# Motor_Driver_HIP4082_Board_V1_1.net
KiCad netlist of a schematic drawn in Altium Designer
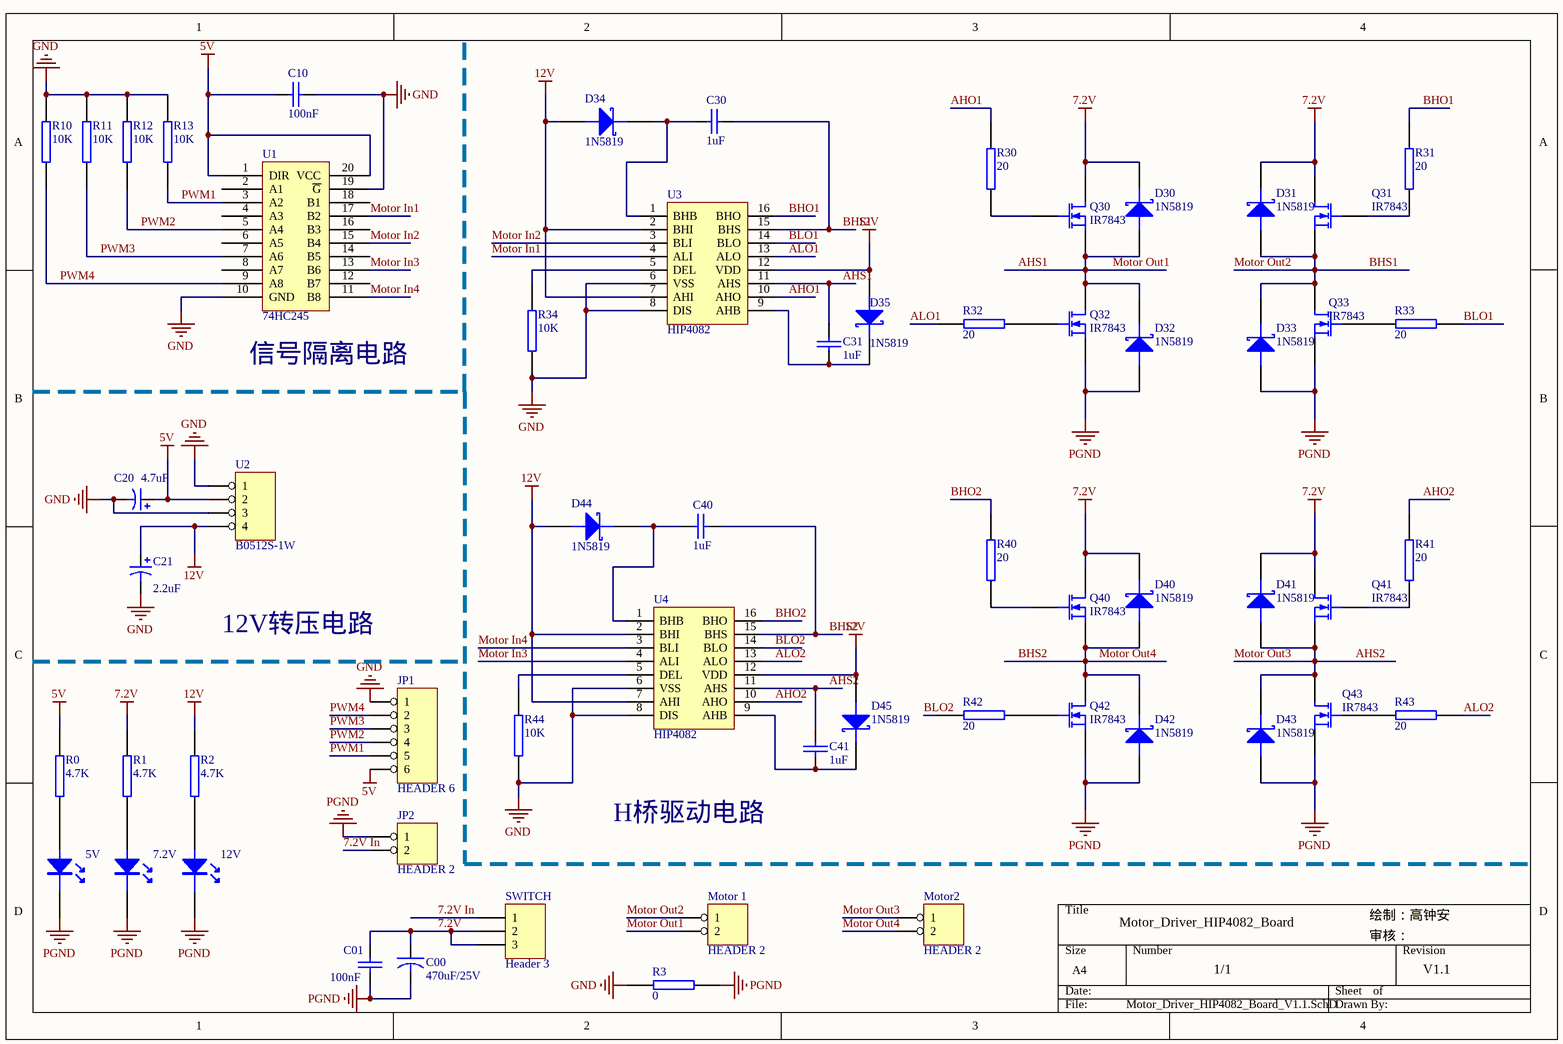
[diagram p0: Motor_Driver_HIP4082_Board_V1.1.SchDoc]

(export (version "E")
  (design (tool "Eeschema 10.0.6"))
  (components
    (comp (ref "5V") (value "~") (footprint "0805_LED_S1") (libsource (lib "Protel99Lib_SCH") (part "LED")))
    (comp (ref "7.2V") (value "~") (footprint "0805_LED_S1") (libsource (lib "Protel99Lib_SCH") (part "LED")))
    (comp (ref "12V") (value "~") (footprint "0805_LED_S1") (libsource (lib "Protel99Lib_SCH") (part "LED")))
    (comp (ref "C00")
      (value "470uF/25V")
      (footprint "RB.2/.4")
      (description "Capacitor")
      (libsource (lib "Protel99Lib_SCH") (part "CAPACITOR"))
    )
    (comp (ref "C01")
      (value "100nF")
      (footprint "0805C")
      (description "Capacitor")
      (libsource (lib "Protel99Lib_SCH") (part "CAP"))
    )
    (comp (ref "C10")
      (value "100nF")
      (footprint "0805C")
      (description "Capacitor")
      (libsource (lib "Protel99Lib_SCH") (part "CAP"))
    )
    (comp (ref "C20")
      (value "4.7uF")
      (footprint "3528")
      (description "Polarized Capacitor (Surface Mount)")
      (fields (field (name "PUBLISHER") "Altium Limited"))
      (libsource (lib "Miscellaneous Devices") (part "Cap Pol3"))
    )
    (comp (ref "C21")
      (value "2.2uF")
      (footprint "3528")
      (description "Polarized Capacitor (Surface Mount)")
      (fields (field (name "PUBLISHER") "Altium Limited"))
      (libsource (lib "Miscellaneous Devices") (part "Cap Pol3"))
    )
    (comp (ref "C30")
      (value "1uF")
      (footprint "0805C")
      (description "Capacitor")
      (libsource (lib "Protel99Lib_SCH") (part "CAP"))
    )
    (comp (ref "C31")
      (value "1uF")
      (footprint "0805C")
      (description "Capacitor")
      (libsource (lib "Protel99Lib_SCH") (part "CAP"))
    )
    (comp (ref "C40")
      (value "1uF")
      (footprint "0805C")
      (description "Capacitor")
      (libsource (lib "Protel99Lib_SCH") (part "CAP"))
    )
    (comp (ref "C41")
      (value "1uF")
      (footprint "0805C")
      (description "Capacitor")
      (libsource (lib "Protel99Lib_SCH") (part "CAP"))
    )
    (comp (ref "D30")
      (value "1N5819")
      (footprint "SOD-323")
      (description "Schottky Diode")
      (libsource (lib "Protel99Lib_SCH") (part "DIODE SCHOTTKY"))
    )
    (comp (ref "D31")
      (value "1N5819")
      (footprint "SOD-323")
      (description "Schottky Diode")
      (libsource (lib "Protel99Lib_SCH") (part "DIODE SCHOTTKY"))
    )
    (comp (ref "D32")
      (value "1N5819")
      (footprint "SOD-323")
      (description "Schottky Diode")
      (libsource (lib "Protel99Lib_SCH") (part "DIODE SCHOTTKY"))
    )
    (comp (ref "D33")
      (value "1N5819")
      (footprint "SOD-323")
      (description "Schottky Diode")
      (libsource (lib "Protel99Lib_SCH") (part "DIODE SCHOTTKY"))
    )
    (comp (ref "D34")
      (value "1N5819")
      (footprint "SOD-323")
      (description "Schottky Diode")
      (libsource (lib "Protel99Lib_SCH") (part "DIODE SCHOTTKY"))
    )
    (comp (ref "D35")
      (value "1N5819")
      (footprint "SOD-323")
      (description "Schottky Diode")
      (libsource (lib "Protel99Lib_SCH") (part "DIODE SCHOTTKY"))
    )
    (comp (ref "D40")
      (value "1N5819")
      (footprint "SOD-323")
      (description "Schottky Diode")
      (libsource (lib "Protel99Lib_SCH") (part "DIODE SCHOTTKY"))
    )
    (comp (ref "D41")
      (value "1N5819")
      (footprint "SOD-323")
      (description "Schottky Diode")
      (libsource (lib "Protel99Lib_SCH") (part "DIODE SCHOTTKY"))
    )
    (comp (ref "D42")
      (value "1N5819")
      (footprint "SOD-323")
      (description "Schottky Diode")
      (libsource (lib "Protel99Lib_SCH") (part "DIODE SCHOTTKY"))
    )
    (comp (ref "D43")
      (value "1N5819")
      (footprint "SOD-323")
      (description "Schottky Diode")
      (libsource (lib "Protel99Lib_SCH") (part "DIODE SCHOTTKY"))
    )
    (comp (ref "D44")
      (value "1N5819")
      (footprint "SOD-323")
      (description "Schottky Diode")
      (libsource (lib "Protel99Lib_SCH") (part "DIODE SCHOTTKY"))
    )
    (comp (ref "D45")
      (value "1N5819")
      (footprint "SOD-323")
      (description "Schottky Diode")
      (libsource (lib "Protel99Lib_SCH") (part "DIODE SCHOTTKY"))
    )
    (comp (ref "JP1")
      (value "HEADER 6")
      (footprint "SIP6N")
      (libsource (lib "Protel99Lib_SCH") (part "HEADER 6"))
    )
    (comp (ref "JP2")
      (value "HEADER 2")
      (footprint "KF301-2P")
      (libsource (lib "Protel99Lib_SCH") (part "HEADER 2"))
    )
    (comp (ref "Motor 1")
      (value "HEADER 2")
      (footprint "KF301-2P")
      (libsource (lib "Protel99Lib_SCH") (part "HEADER 2"))
    )
    (comp (ref "Motor2")
      (value "HEADER 2")
      (footprint "KF301-2P")
      (libsource (lib "Protel99Lib_SCH") (part "HEADER 2"))
    )
    (comp (ref "Q30")
      (value "IR7843")
      (footprint "LR7843")
      (description "N-Channel MOSFET")
      (fields (field (name "PUBLISHER") "Altium Limited"))
      (libsource (lib "Miscellaneous Devices") (part "MOSFET-N"))
    )
    (comp (ref "Q31")
      (value "IR7843")
      (footprint "LR7843")
      (description "N-Channel MOSFET")
      (fields (field (name "PUBLISHER") "Altium Limited"))
      (libsource (lib "Miscellaneous Devices") (part "MOSFET-N"))
    )
    (comp (ref "Q32")
      (value "IR7843")
      (footprint "LR7843")
      (description "N-Channel MOSFET")
      (fields (field (name "PUBLISHER") "Altium Limited"))
      (libsource (lib "Miscellaneous Devices") (part "MOSFET-N"))
    )
    (comp (ref "Q33")
      (value "IR7843")
      (footprint "LR7843")
      (description "N-Channel MOSFET")
      (fields (field (name "PUBLISHER") "Altium Limited"))
      (libsource (lib "Miscellaneous Devices") (part "MOSFET-N"))
    )
    (comp (ref "Q40")
      (value "IR7843")
      (footprint "LR7843")
      (description "N-Channel MOSFET")
      (fields (field (name "PUBLISHER") "Altium Limited"))
      (libsource (lib "Miscellaneous Devices") (part "MOSFET-N"))
    )
    (comp (ref "Q41")
      (value "IR7843")
      (footprint "LR7843")
      (description "N-Channel MOSFET")
      (fields (field (name "PUBLISHER") "Altium Limited"))
      (libsource (lib "Miscellaneous Devices") (part "MOSFET-N"))
    )
    (comp (ref "Q42")
      (value "IR7843")
      (footprint "LR7843")
      (description "N-Channel MOSFET")
      (fields (field (name "PUBLISHER") "Altium Limited"))
      (libsource (lib "Miscellaneous Devices") (part "MOSFET-N"))
    )
    (comp (ref "Q43")
      (value "IR7843")
      (footprint "LR7843")
      (description "N-Channel MOSFET")
      (fields (field (name "PUBLISHER") "Altium Limited"))
      (libsource (lib "Miscellaneous Devices") (part "MOSFET-N"))
    )
    (comp (ref "R0") (value "4.7K") (footprint "0603_R") (libsource (lib "Protel99Lib_SCH") (part "RES2")))
    (comp (ref "R1") (value "4.7K") (footprint "0603_R") (libsource (lib "Protel99Lib_SCH") (part "RES2")))
    (comp (ref "R2") (value "4.7K") (footprint "0603_R") (libsource (lib "Protel99Lib_SCH") (part "RES2")))
    (comp (ref "R3") (value "0") (footprint "0805R") (libsource (lib "Protel99Lib_SCH") (part "RES2")))
    (comp (ref "R10") (value "10K") (footprint "0603_R") (libsource (lib "") (part "RES2_1")))
    (comp (ref "R11") (value "10K") (footprint "0603_R") (libsource (lib "") (part "RES2_1")))
    (comp (ref "R12") (value "10K") (footprint "0603_R") (libsource (lib "") (part "RES2_1")))
    (comp (ref "R13") (value "10K") (footprint "0603_R") (libsource (lib "") (part "RES2_1")))
    (comp (ref "R30") (value "20") (footprint "0805") (libsource (lib "Protel99Lib_SCH") (part "RES2")))
    (comp (ref "R31") (value "20") (footprint "0805") (libsource (lib "Protel99Lib_SCH") (part "RES2")))
    (comp (ref "R32") (value "20") (footprint "0805") (libsource (lib "Protel99Lib_SCH") (part "RES2")))
    (comp (ref "R33") (value "20") (footprint "0805") (libsource (lib "Protel99Lib_SCH") (part "RES2")))
    (comp (ref "R34") (value "10K") (footprint "0603_R") (libsource (lib "Protel99Lib_SCH") (part "RES2")))
    (comp (ref "R40") (value "20") (footprint "0805") (libsource (lib "Protel99Lib_SCH") (part "RES2")))
    (comp (ref "R41") (value "20") (footprint "0805") (libsource (lib "Protel99Lib_SCH") (part "RES2")))
    (comp (ref "R42") (value "20") (footprint "0805") (libsource (lib "Protel99Lib_SCH") (part "RES2")))
    (comp (ref "R43") (value "20") (footprint "0805") (libsource (lib "Protel99Lib_SCH") (part "RES2")))
    (comp (ref "R44") (value "10K") (footprint "0603_R") (libsource (lib "Protel99Lib_SCH") (part "RES2")))
    (comp (ref "SWITCH")
      (value "Header 3")
      (footprint "KEY-3P")
      (description "Header, 3-Pin")
      (fields (field (name "PUBLISHER") "Altium Limited"))
      (libsource (lib "Miscellaneous Connectors") (part "Header 3"))
    )
    (comp (ref "U1") (value "74HC245") (footprint "SOP20") (libsource (lib "BaseLib_SCH") (part "74HC245")))
    (comp (ref "U2")
      (value "B0512S-1W")
      (footprint "SIP4_B_S-1W")
      (description "4 Pin Header")
      (libsource (lib "Protel99Lib_SCH") (part "4 HEADER"))
    )
    (comp (ref "U3")
      (value "HIP4082")
      (footprint "SOP-16_208mil")
      (libsource (lib "Motor_Driver_HIP4082_Board_V1.0") (part "HIP4082"))
    )
    (comp (ref "U4")
      (value "HIP4082")
      (footprint "SOP-16_208mil")
      (libsource (lib "Motor_Driver_HIP4082_Board_V1.0") (part "HIP4082"))
    )
  )
  (nets
    (net (code "1") (name "/7.2V In") (class "Default")
      (node (ref "JP2") (pin "2") (pinfunction "2_2") (pintype "passive"))
      (node (ref "SWITCH") (pin "1") (pinfunction "1_1") (pintype "passive"))
    )
    (net (code "2") (name "/AHO1") (class "Default")
      (node (ref "R30") (pin "2") (pinfunction "2_2") (pintype "passive"))
      (node (ref "U3") (pin "10") (pinfunction "AHO_10") (pintype "passive"))
    )
    (net (code "3") (name "/AHO2") (class "Default")
      (node (ref "R41") (pin "2") (pinfunction "2_2") (pintype "passive"))
      (node (ref "U4") (pin "10") (pinfunction "AHO_10") (pintype "passive"))
    )
    (net (code "4") (name "/AHS1") (class "Default")
      (node (ref "C31") (pin "2") (pinfunction "2_2") (pintype "passive"))
      (node (ref "D30") (pin "1") (pinfunction "A_1") (pintype "passive"))
      (node (ref "D32") (pin "2") (pinfunction "K_2") (pintype "passive"))
      (node (ref "Motor 1") (pin "2") (pinfunction "2_2") (pintype "passive"))
      (node (ref "Q30") (pin "3") (pinfunction "S_3") (pintype "passive"))
      (node (ref "Q32") (pin "1") (pinfunction "D_1") (pintype "passive"))
      (node (ref "U3") (pin "11") (pinfunction "AHS_11") (pintype "passive"))
    )
    (net (code "5") (name "/AHS2") (class "Default")
      (node (ref "C41") (pin "2") (pinfunction "2_2") (pintype "passive"))
      (node (ref "D41") (pin "1") (pinfunction "A_1") (pintype "passive"))
      (node (ref "D43") (pin "2") (pinfunction "K_2") (pintype "passive"))
      (node (ref "Motor2") (pin "1") (pinfunction "1_1") (pintype "passive"))
      (node (ref "Q41") (pin "3") (pinfunction "S_3") (pintype "passive"))
      (node (ref "Q43") (pin "1") (pinfunction "D_1") (pintype "passive"))
      (node (ref "U4") (pin "11") (pinfunction "AHS_11") (pintype "passive"))
    )
    (net (code "6") (name "/ALO1") (class "Default")
      (node (ref "R32") (pin "2") (pinfunction "2_2") (pintype "passive"))
      (node (ref "U3") (pin "13") (pinfunction "ALO_13") (pintype "passive"))
    )
    (net (code "7") (name "/ALO2") (class "Default")
      (node (ref "R43") (pin "1") (pinfunction "1_1") (pintype "passive"))
      (node (ref "U4") (pin "13") (pinfunction "ALO_13") (pintype "passive"))
    )
    (net (code "8") (name "/BHO1") (class "Default")
      (node (ref "R31") (pin "2") (pinfunction "2_2") (pintype "passive"))
      (node (ref "U3") (pin "16") (pinfunction "BHO_16") (pintype "passive"))
    )
    (net (code "9") (name "/BHO2") (class "Default")
      (node (ref "R40") (pin "2") (pinfunction "2_2") (pintype "passive"))
      (node (ref "U4") (pin "16") (pinfunction "BHO_16") (pintype "passive"))
    )
    (net (code "10") (name "/BHS1") (class "Default")
      (node (ref "C30") (pin "2") (pinfunction "2_2") (pintype "passive"))
      (node (ref "D31") (pin "1") (pinfunction "A_1") (pintype "passive"))
      (node (ref "D33") (pin "2") (pinfunction "K_2") (pintype "passive"))
      (node (ref "Motor 1") (pin "1") (pinfunction "1_1") (pintype "passive"))
      (node (ref "Q31") (pin "3") (pinfunction "S_3") (pintype "passive"))
      (node (ref "Q33") (pin "1") (pinfunction "D_1") (pintype "passive"))
      (node (ref "U3") (pin "15") (pinfunction "BHS_15") (pintype "passive"))
    )
    (net (code "11") (name "/BHS2") (class "Default")
      (node (ref "C40") (pin "2") (pinfunction "2_2") (pintype "passive"))
      (node (ref "D40") (pin "1") (pinfunction "A_1") (pintype "passive"))
      (node (ref "D42") (pin "2") (pinfunction "K_2") (pintype "passive"))
      (node (ref "Motor2") (pin "2") (pinfunction "2_2") (pintype "passive"))
      (node (ref "Q40") (pin "3") (pinfunction "S_3") (pintype "passive"))
      (node (ref "Q42") (pin "1") (pinfunction "D_1") (pintype "passive"))
      (node (ref "U4") (pin "15") (pinfunction "BHS_15") (pintype "passive"))
    )
    (net (code "12") (name "/BLO1") (class "Default")
      (node (ref "R33") (pin "1") (pinfunction "1_1") (pintype "passive"))
      (node (ref "U3") (pin "14") (pinfunction "BLO_14") (pintype "passive"))
    )
    (net (code "13") (name "/BLO2") (class "Default")
      (node (ref "R42") (pin "2") (pinfunction "2_2") (pintype "passive"))
      (node (ref "U4") (pin "14") (pinfunction "BLO_14") (pintype "passive"))
    )
    (net (code "14") (name "/Motor In1") (class "Default")
      (node (ref "U1") (pin "17") (pinfunction "B2_17") (pintype "passive"))
      (node (ref "U3") (pin "4") (pinfunction "ALI_4") (pintype "passive"))
    )
    (net (code "15") (name "/Motor In2") (class "Default")
      (node (ref "U1") (pin "15") (pinfunction "B4_15") (pintype "passive"))
      (node (ref "U3") (pin "3") (pinfunction "BLI_3") (pintype "passive"))
    )
    (net (code "16") (name "/Motor In3") (class "Default")
      (node (ref "U1") (pin "13") (pinfunction "B6_13") (pintype "passive"))
      (node (ref "U4") (pin "4") (pinfunction "ALI_4") (pintype "passive"))
    )
    (net (code "17") (name "/Motor In4") (class "Default")
      (node (ref "U1") (pin "11") (pinfunction "B8_11") (pintype "passive"))
      (node (ref "U4") (pin "3") (pinfunction "BLI_3") (pintype "passive"))
    )
    (net (code "18") (name "/PWM1") (class "Default")
      (node (ref "JP1") (pin "5") (pinfunction "5_5") (pintype "passive"))
      (node (ref "R13") (pin "1") (pinfunction "1_1") (pintype "passive"))
      (node (ref "U1") (pin "3") (pinfunction "A2_3") (pintype "passive"))
    )
    (net (code "19") (name "/PWM2") (class "Default")
      (node (ref "JP1") (pin "4") (pinfunction "4_4") (pintype "passive"))
      (node (ref "R12") (pin "1") (pinfunction "1_1") (pintype "passive"))
      (node (ref "U1") (pin "5") (pinfunction "A4_5") (pintype "passive"))
    )
    (net (code "20") (name "/PWM3") (class "Default")
      (node (ref "JP1") (pin "3") (pinfunction "3_3") (pintype "passive"))
      (node (ref "R11") (pin "2") (pinfunction "2_2") (pintype "passive"))
      (node (ref "U1") (pin "7") (pinfunction "A6_7") (pintype "passive"))
    )
    (net (code "21") (name "/PWM4") (class "Default")
      (node (ref "JP1") (pin "2") (pinfunction "2_2") (pintype "passive"))
      (node (ref "R10") (pin "1") (pinfunction "1_1") (pintype "passive"))
      (node (ref "U1") (pin "9") (pinfunction "A8_9") (pintype "passive"))
    )
    (net (code "22") (name "5V") (class "Default")
      (node (ref "C10") (pin "1") (pinfunction "1_1") (pintype "passive"))
      (node (ref "C20") (pin "1") (pinfunction "1_1") (pintype "passive"))
      (node (ref "JP1") (pin "6") (pinfunction "6_6") (pintype "passive"))
      (node (ref "R0") (pin "2") (pinfunction "2_2") (pintype "passive"))
      (node (ref "U1") (pin "1") (pinfunction "DIR_1") (pintype "passive"))
      (node (ref "U1") (pin "20") (pinfunction "VCC_20") (pintype "passive"))
      (node (ref "U2") (pin "2") (pinfunction "2_2") (pintype "passive"))
    )
    (net (code "23") (name "7.2V") (class "Default")
      (node (ref "C00") (pin "1") (pinfunction "1_1") (pintype "passive"))
      (node (ref "C01") (pin "2") (pinfunction "2_2") (pintype "passive"))
      (node (ref "D30") (pin "2") (pinfunction "K_2") (pintype "passive"))
      (node (ref "D31") (pin "2") (pinfunction "K_2") (pintype "passive"))
      (node (ref "D40") (pin "2") (pinfunction "K_2") (pintype "passive"))
      (node (ref "D41") (pin "2") (pinfunction "K_2") (pintype "passive"))
      (node (ref "Q30") (pin "1") (pinfunction "D_1") (pintype "passive"))
      (node (ref "Q31") (pin "1") (pinfunction "D_1") (pintype "passive"))
      (node (ref "Q40") (pin "1") (pinfunction "D_1") (pintype "passive"))
      (node (ref "Q41") (pin "1") (pinfunction "D_1") (pintype "passive"))
      (node (ref "R1") (pin "2") (pinfunction "2_2") (pintype "passive"))
      (node (ref "SWITCH") (pin "2") (pinfunction "2_2") (pintype "passive"))
      (node (ref "SWITCH") (pin "3") (pinfunction "3_3") (pintype "passive"))
    )
    (net (code "24") (name "12V") (class "Default")
      (node (ref "C21") (pin "1") (pinfunction "1_1") (pintype "passive"))
      (node (ref "D34") (pin "1") (pinfunction "A_1") (pintype "passive"))
      (node (ref "D35") (pin "1") (pinfunction "A_1") (pintype "passive"))
      (node (ref "D44") (pin "1") (pinfunction "A_1") (pintype "passive"))
      (node (ref "D45") (pin "1") (pinfunction "A_1") (pintype "passive"))
      (node (ref "R2") (pin "2") (pinfunction "2_2") (pintype "passive"))
      (node (ref "U2") (pin "4") (pinfunction "4_4") (pintype "passive"))
      (node (ref "U3") (pin "12") (pinfunction "VDD_12") (pintype "passive"))
      (node (ref "U3") (pin "2") (pinfunction "BHI_2") (pintype "passive"))
      (node (ref "U3") (pin "7") (pinfunction "AHI_7") (pintype "passive"))
      (node (ref "U4") (pin "12") (pinfunction "VDD_12") (pintype "passive"))
      (node (ref "U4") (pin "2") (pinfunction "BHI_2") (pintype "passive"))
      (node (ref "U4") (pin "7") (pinfunction "AHI_7") (pintype "passive"))
    )
    (net (code "25") (name "GND") (class "Default")
      (node (ref "C10") (pin "2") (pinfunction "2_2") (pintype "passive"))
      (node (ref "C20") (pin "2") (pinfunction "2_2") (pintype "passive"))
      (node (ref "C21") (pin "2") (pinfunction "2_2") (pintype "passive"))
      (node (ref "JP1") (pin "1") (pinfunction "1_1") (pintype "passive"))
      (node (ref "R10") (pin "2") (pinfunction "2_2") (pintype "passive"))
      (node (ref "R11") (pin "1") (pinfunction "1_1") (pintype "passive"))
      (node (ref "R12") (pin "2") (pinfunction "2_2") (pintype "passive"))
      (node (ref "R13") (pin "2") (pinfunction "2_2") (pintype "passive"))
      (node (ref "R3") (pin "2") (pinfunction "2_2") (pintype "passive"))
      (node (ref "R34") (pin "1") (pinfunction "1_1") (pintype "passive"))
      (node (ref "R44") (pin "1") (pinfunction "1_1") (pintype "passive"))
      (node (ref "U1") (pin "10") (pinfunction "GND_10") (pintype "passive"))
      (node (ref "U1") (pin "19") (pinfunction "~{G}_19") (pintype "passive"))
      (node (ref "U2") (pin "1") (pinfunction "1_1") (pintype "passive"))
      (node (ref "U2") (pin "3") (pinfunction "3_3") (pintype "passive"))
      (node (ref "U3") (pin "6") (pinfunction "VSS_6") (pintype "passive"))
      (node (ref "U3") (pin "8") (pinfunction "DIS_8") (pintype "passive"))
      (node (ref "U4") (pin "6") (pinfunction "VSS_6") (pintype "passive"))
      (node (ref "U4") (pin "8") (pinfunction "DIS_8") (pintype "passive"))
    )
    (net (code "26") (name "Net-(5V-1)") (class "Default")
      (node (ref "5V") (pin "A") (pinfunction "1_A") (pintype "passive"))
      (node (ref "R0") (pin "1") (pinfunction "1_1") (pintype "passive"))
    )
    (net (code "27") (name "Net-(7.2V-1)") (class "Default")
      (node (ref "7.2V") (pin "A") (pinfunction "1_A") (pintype "passive"))
      (node (ref "R1") (pin "1") (pinfunction "1_1") (pintype "passive"))
    )
    (net (code "28") (name "Net-(12V-1)") (class "Default")
      (node (ref "12V") (pin "A") (pinfunction "1_A") (pintype "passive"))
      (node (ref "R2") (pin "1") (pinfunction "1_1") (pintype "passive"))
    )
    (net (code "29") (name "Net-(D34-K)") (class "Default")
      (node (ref "C30") (pin "1") (pinfunction "1_1") (pintype "passive"))
      (node (ref "D34") (pin "2") (pinfunction "K_2") (pintype "passive"))
      (node (ref "U3") (pin "1") (pinfunction "BHB_1") (pintype "passive"))
    )
    (net (code "30") (name "Net-(D35-K)") (class "Default")
      (node (ref "C31") (pin "1") (pinfunction "1_1") (pintype "passive"))
      (node (ref "D35") (pin "2") (pinfunction "K_2") (pintype "passive"))
      (node (ref "U3") (pin "9") (pinfunction "AHB_9") (pintype "passive"))
    )
    (net (code "31") (name "Net-(D44-K)") (class "Default")
      (node (ref "C40") (pin "1") (pinfunction "1_1") (pintype "passive"))
      (node (ref "D44") (pin "2") (pinfunction "K_2") (pintype "passive"))
      (node (ref "U4") (pin "1") (pinfunction "BHB_1") (pintype "passive"))
    )
    (net (code "32") (name "Net-(D45-K)") (class "Default")
      (node (ref "C41") (pin "1") (pinfunction "1_1") (pintype "passive"))
      (node (ref "D45") (pin "2") (pinfunction "K_2") (pintype "passive"))
      (node (ref "U4") (pin "9") (pinfunction "AHB_9") (pintype "passive"))
    )
    (net (code "33") (name "Net-(Q30-G)") (class "Default")
      (node (ref "Q30") (pin "2") (pinfunction "G_2") (pintype "passive"))
      (node (ref "R30") (pin "1") (pinfunction "1_1") (pintype "passive"))
    )
    (net (code "34") (name "Net-(Q31-G)") (class "Default")
      (node (ref "Q31") (pin "2") (pinfunction "G_2") (pintype "passive"))
      (node (ref "R31") (pin "1") (pinfunction "1_1") (pintype "passive"))
    )
    (net (code "35") (name "Net-(Q32-G)") (class "Default")
      (node (ref "Q32") (pin "2") (pinfunction "G_2") (pintype "passive"))
      (node (ref "R32") (pin "1") (pinfunction "1_1") (pintype "passive"))
    )
    (net (code "36") (name "Net-(Q33-G)") (class "Default")
      (node (ref "Q33") (pin "2") (pinfunction "G_2") (pintype "passive"))
      (node (ref "R33") (pin "2") (pinfunction "2_2") (pintype "passive"))
    )
    (net (code "37") (name "Net-(Q40-G)") (class "Default")
      (node (ref "Q40") (pin "2") (pinfunction "G_2") (pintype "passive"))
      (node (ref "R40") (pin "1") (pinfunction "1_1") (pintype "passive"))
    )
    (net (code "38") (name "Net-(Q41-G)") (class "Default")
      (node (ref "Q41") (pin "2") (pinfunction "G_2") (pintype "passive"))
      (node (ref "R41") (pin "1") (pinfunction "1_1") (pintype "passive"))
    )
    (net (code "39") (name "Net-(Q42-G)") (class "Default")
      (node (ref "Q42") (pin "2") (pinfunction "G_2") (pintype "passive"))
      (node (ref "R42") (pin "1") (pinfunction "1_1") (pintype "passive"))
    )
    (net (code "40") (name "Net-(Q43-G)") (class "Default")
      (node (ref "Q43") (pin "2") (pinfunction "G_2") (pintype "passive"))
      (node (ref "R43") (pin "2") (pinfunction "2_2") (pintype "passive"))
    )
    (net (code "41") (name "Net-(U3-DEL)") (class "Default")
      (node (ref "R34") (pin "2") (pinfunction "2_2") (pintype "passive"))
      (node (ref "U3") (pin "5") (pinfunction "DEL_5") (pintype "passive"))
    )
    (net (code "42") (name "Net-(U4-DEL)") (class "Default")
      (node (ref "R44") (pin "2") (pinfunction "2_2") (pintype "passive"))
      (node (ref "U4") (pin "5") (pinfunction "DEL_5") (pintype "passive"))
    )
    (net (code "43") (name "PGND") (class "Default")
      (node (ref "12V") (pin "K") (pinfunction "2_K") (pintype "passive"))
      (node (ref "5V") (pin "K") (pinfunction "2_K") (pintype "passive"))
      (node (ref "7.2V") (pin "K") (pinfunction "2_K") (pintype "passive"))
      (node (ref "C00") (pin "2") (pinfunction "2_2") (pintype "passive"))
      (node (ref "C01") (pin "1") (pinfunction "1_1") (pintype "passive"))
      (node (ref "D32") (pin "1") (pinfunction "A_1") (pintype "passive"))
      (node (ref "D33") (pin "1") (pinfunction "A_1") (pintype "passive"))
      (node (ref "D42") (pin "1") (pinfunction "A_1") (pintype "passive"))
      (node (ref "D43") (pin "1") (pinfunction "A_1") (pintype "passive"))
      (node (ref "JP2") (pin "1") (pinfunction "1_1") (pintype "passive"))
      (node (ref "Q32") (pin "3") (pinfunction "S_3") (pintype "passive"))
      (node (ref "Q33") (pin "3") (pinfunction "S_3") (pintype "passive"))
      (node (ref "Q42") (pin "3") (pinfunction "S_3") (pintype "passive"))
      (node (ref "Q43") (pin "3") (pinfunction "S_3") (pintype "passive"))
      (node (ref "R3") (pin "1") (pinfunction "1_1") (pintype "passive"))
    )
    (net (code "44") (name "unconnected-(U1-A1-Pad2)") (class "Default")
      (node (ref "U1") (pin "2") (pinfunction "A1_2") (pintype "passive"))
    )
    (net (code "45") (name "unconnected-(U1-A3-Pad4)") (class "Default")
      (node (ref "U1") (pin "4") (pinfunction "A3_4") (pintype "passive"))
    )
    (net (code "46") (name "unconnected-(U1-A5-Pad6)") (class "Default")
      (node (ref "U1") (pin "6") (pinfunction "A5_6") (pintype "passive"))
    )
    (net (code "47") (name "unconnected-(U1-A7-Pad8)") (class "Default")
      (node (ref "U1") (pin "8") (pinfunction "A7_8") (pintype "passive"))
    )
    (net (code "48") (name "unconnected-(U1-B1-Pad18)") (class "Default")
      (node (ref "U1") (pin "18") (pinfunction "B1_18") (pintype "passive"))
    )
    (net (code "49") (name "unconnected-(U1-B3-Pad16)") (class "Default")
      (node (ref "U1") (pin "16") (pinfunction "B3_16") (pintype "passive"))
    )
    (net (code "50") (name "unconnected-(U1-B5-Pad14)") (class "Default")
      (node (ref "U1") (pin "14") (pinfunction "B5_14") (pintype "passive"))
    )
    (net (code "51") (name "unconnected-(U1-B7-Pad12)") (class "Default")
      (node (ref "U1") (pin "12") (pinfunction "B7_12") (pintype "passive"))
    )
  )
)
